# 31_Power2.net
KiCad netlist of a schematic drawn in Altium Designer
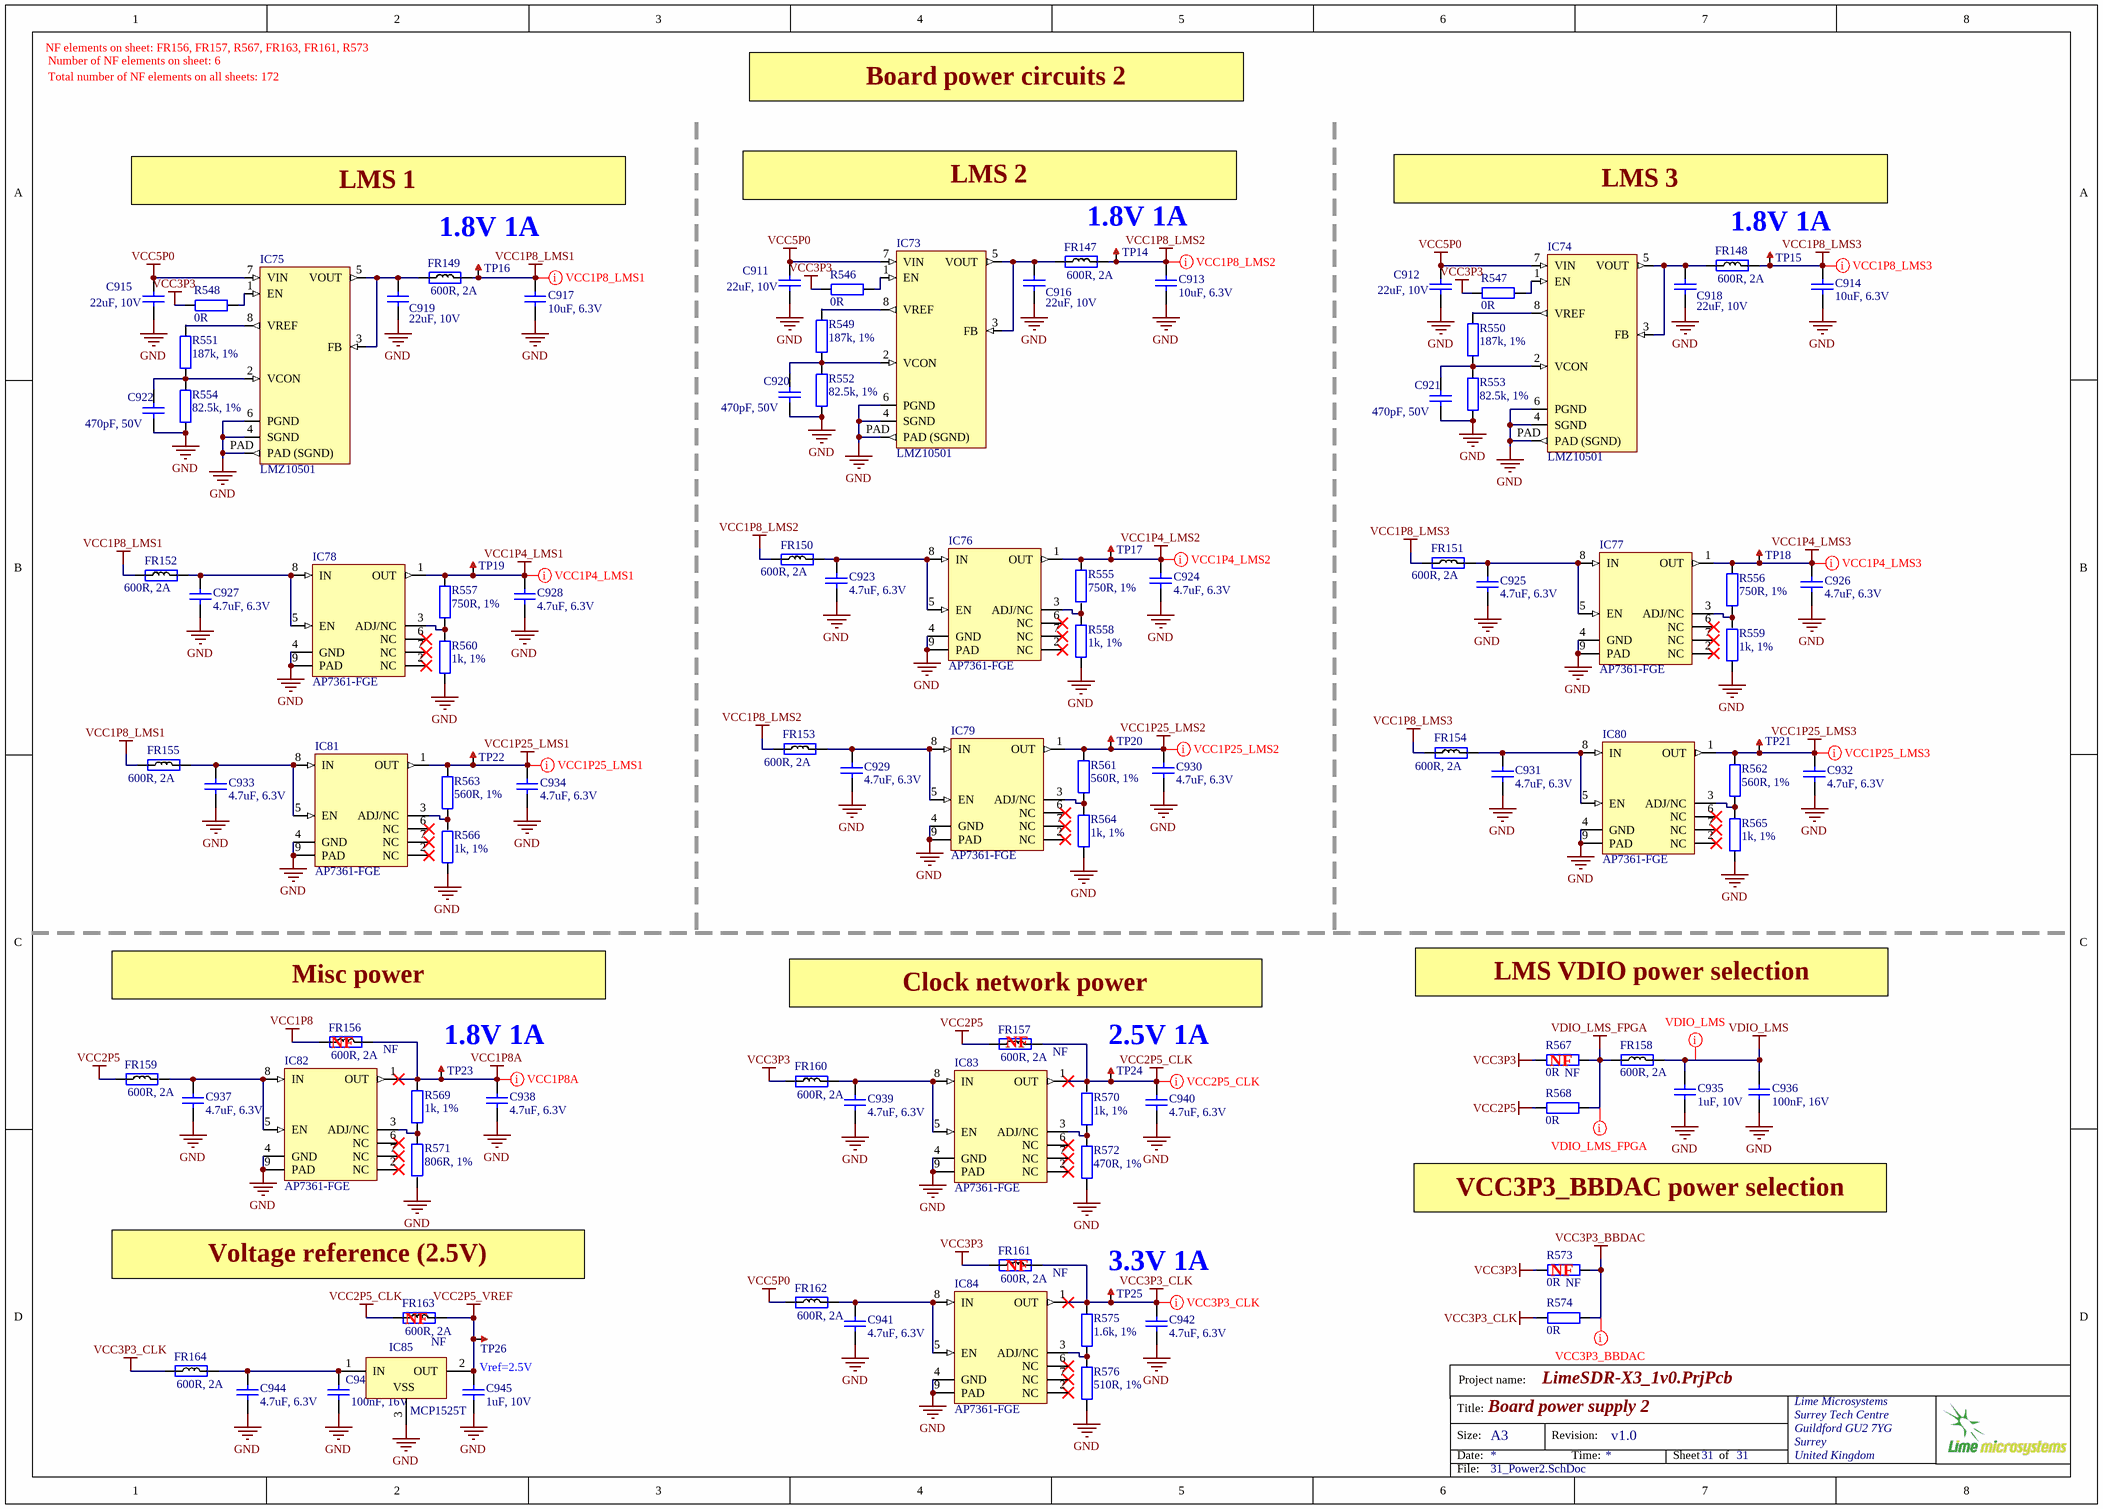
[diagram p0: 31_Power2.SchDoc]

(export (version "E")
  (design (tool "Eeschema 10.0.6"))
  (components
    (comp (ref "C911")
      (value "22uF, 10V")
      (footprint "CAP0603")
      (fields (field (name "TOLERANCE") "20 %") (field (name "MANUFACTURER") "TDK Corporation"))
      (libsource (lib "LimeFPGAboard_schLib") (part "Cap_0603"))
    )
    (comp (ref "C912")
      (value "22uF, 10V")
      (footprint "CAP0603")
      (fields (field (name "TOLERANCE") "20 %") (field (name "MANUFACTURER") "TDK Corporation"))
      (libsource (lib "LimeFPGAboard_schLib") (part "Cap_0603"))
    )
    (comp (ref "C913")
      (value "10uF, 6.3V")
      (footprint "CAP0603")
      (fields (field (name "TOLERANCE") "±20%") (field (name "MANUFACTURER") "Yageo"))
      (libsource (lib "LimeFPGAboard_schLib") (part "Cap_0603"))
    )
    (comp (ref "C914")
      (value "10uF, 6.3V")
      (footprint "CAP0603")
      (fields (field (name "TOLERANCE") "±20%") (field (name "MANUFACTURER") "Yageo"))
      (libsource (lib "LimeFPGAboard_schLib") (part "Cap_0603"))
    )
    (comp (ref "C915")
      (value "22uF, 10V")
      (footprint "CAP0603")
      (fields (field (name "TOLERANCE") "20 %") (field (name "MANUFACTURER") "TDK Corporation"))
      (libsource (lib "LimeFPGAboard_schLib") (part "Cap_0603"))
    )
    (comp (ref "C916")
      (value "22uF, 10V")
      (footprint "CAP0603")
      (fields (field (name "TOLERANCE") "20 %") (field (name "MANUFACTURER") "TDK Corporation"))
      (libsource (lib "LimeFPGAboard_schLib") (part "Cap_0603"))
    )
    (comp (ref "C917")
      (value "10uF, 6.3V")
      (footprint "CAP0603")
      (fields (field (name "TOLERANCE") "±20%") (field (name "MANUFACTURER") "Yageo"))
      (libsource (lib "") (part "Cap_0603_1"))
    )
    (comp (ref "C918")
      (value "22uF, 10V")
      (footprint "CAP0603")
      (fields (field (name "TOLERANCE") "20 %") (field (name "MANUFACTURER") "TDK Corporation"))
      (libsource (lib "LimeFPGAboard_schLib") (part "Cap_0603"))
    )
    (comp (ref "C919")
      (value "22uF, 10V")
      (footprint "CAP0603")
      (fields (field (name "TOLERANCE") "20 %") (field (name "MANUFACTURER") "TDK Corporation"))
      (libsource (lib "LimeFPGAboard_schLib") (part "Cap_0603"))
    )
    (comp (ref "C920")
      (value "470pF, 50V")
      (footprint "CAP0402")
      (fields
        (field (name "TOLERANCE") "±5%")
        (field (name "MANUFACTURER") "TDK Corporation")
        (field (name "MANUFACTURER PART NUMBER") "C1005C0G1H471J050BA")
      )
      (libsource (lib "") (part "Cap_0402_5"))
    )
    (comp (ref "C921")
      (value "470pF, 50V")
      (footprint "CAP0402")
      (fields
        (field (name "TOLERANCE") "±5%")
        (field (name "MANUFACTURER") "TDK Corporation")
        (field (name "MANUFACTURER PART NUMBER") "C1005C0G1H471J050BA")
      )
      (libsource (lib "") (part "Cap_0402_5"))
    )
    (comp (ref "C922")
      (value "470pF, 50V")
      (footprint "CAP0402")
      (fields
        (field (name "TOLERANCE") "±5%")
        (field (name "MANUFACTURER") "TDK Corporation")
        (field (name "MANUFACTURER PART NUMBER") "C1005C0G1H471J050BA")
      )
      (libsource (lib "") (part "Cap_0402_5"))
    )
    (comp (ref "C923")
      (value "4.7uF, 6.3V")
      (footprint "CAP0402")
      (fields
        (field (name "MANUFACTURER") "Murata Electronics North America")
        (field (name "TOLERANCE") "±20%")
      )
      (libsource (lib "") (part "Cap_0402_1"))
    )
    (comp (ref "C924")
      (value "4.7uF, 6.3V")
      (footprint "CAP0402")
      (fields
        (field (name "MANUFACTURER") "Murata Electronics North America")
        (field (name "TOLERANCE") "±20%")
      )
      (libsource (lib "") (part "Cap_0402_1"))
    )
    (comp (ref "C925")
      (value "4.7uF, 6.3V")
      (footprint "CAP0402")
      (fields
        (field (name "MANUFACTURER") "Murata Electronics North America")
        (field (name "TOLERANCE") "±20%")
      )
      (libsource (lib "") (part "Cap_0402_1"))
    )
    (comp (ref "C926")
      (value "4.7uF, 6.3V")
      (footprint "CAP0402")
      (fields
        (field (name "MANUFACTURER") "Murata Electronics North America")
        (field (name "TOLERANCE") "±20%")
      )
      (libsource (lib "") (part "Cap_0402_1"))
    )
    (comp (ref "C927")
      (value "4.7uF, 6.3V")
      (footprint "CAP0402")
      (fields
        (field (name "MANUFACTURER") "Murata Electronics North America")
        (field (name "TOLERANCE") "±20%")
      )
      (libsource (lib "") (part "Cap_0402_2"))
    )
    (comp (ref "C928")
      (value "4.7uF, 6.3V")
      (footprint "CAP0402")
      (fields
        (field (name "MANUFACTURER") "Murata Electronics North America")
        (field (name "TOLERANCE") "±20%")
      )
      (libsource (lib "") (part "Cap_0402_2"))
    )
    (comp (ref "C929")
      (value "4.7uF, 6.3V")
      (footprint "CAP0402")
      (fields
        (field (name "MANUFACTURER") "Murata Electronics North America")
        (field (name "TOLERANCE") "±20%")
      )
      (libsource (lib "") (part "Cap_0402_1"))
    )
    (comp (ref "C930")
      (value "4.7uF, 6.3V")
      (footprint "CAP0402")
      (fields
        (field (name "MANUFACTURER") "Murata Electronics North America")
        (field (name "TOLERANCE") "±20%")
      )
      (libsource (lib "") (part "Cap_0402_1"))
    )
    (comp (ref "C931")
      (value "4.7uF, 6.3V")
      (footprint "CAP0402")
      (fields
        (field (name "MANUFACTURER") "Murata Electronics North America")
        (field (name "TOLERANCE") "±20%")
      )
      (libsource (lib "") (part "Cap_0402_5"))
    )
    (comp (ref "C932")
      (value "4.7uF, 6.3V")
      (footprint "CAP0402")
      (fields
        (field (name "MANUFACTURER") "Murata Electronics North America")
        (field (name "TOLERANCE") "±20%")
      )
      (libsource (lib "") (part "Cap_0402_1"))
    )
    (comp (ref "C933")
      (value "4.7uF, 6.3V")
      (footprint "CAP0402")
      (fields
        (field (name "MANUFACTURER") "Murata Electronics North America")
        (field (name "TOLERANCE") "±20%")
      )
      (libsource (lib "") (part "Cap_0402_1"))
    )
    (comp (ref "C934")
      (value "4.7uF, 6.3V")
      (footprint "CAP0402")
      (fields
        (field (name "MANUFACTURER") "Murata Electronics North America")
        (field (name "TOLERANCE") "±20%")
      )
      (libsource (lib "") (part "Cap_0402_2"))
    )
    (comp (ref "C935")
      (value "1uF, 10V")
      (footprint "CAP0402")
      (fields (field (name "MANUFACTURER") "TDK"))
      (libsource (lib "") (part "Cap_0402_2"))
    )
    (comp (ref "C936")
      (value "100nF, 16V")
      (footprint "CAP0402")
      (fields (field (name "MANUFACTURER") "Murata Electronics") (field (name "TOLERANCE") "10 %"))
      (libsource (lib "") (part "Cap_0402_2"))
    )
    (comp (ref "C937")
      (value "4.7uF, 6.3V")
      (footprint "CAP0402")
      (fields
        (field (name "MANUFACTURER") "Murata Electronics North America")
        (field (name "TOLERANCE") "±20%")
      )
      (libsource (lib "") (part "Cap_0402_3"))
    )
    (comp (ref "C938")
      (value "4.7uF, 6.3V")
      (footprint "CAP0402")
      (fields
        (field (name "MANUFACTURER") "Murata Electronics North America")
        (field (name "TOLERANCE") "±20%")
      )
      (libsource (lib "") (part "Cap_0402_3"))
    )
    (comp (ref "C939")
      (value "4.7uF, 6.3V")
      (footprint "CAP0402")
      (fields
        (field (name "MANUFACTURER") "Murata Electronics North America")
        (field (name "TOLERANCE") "±20%")
      )
      (libsource (lib "") (part "Cap_0402_1"))
    )
    (comp (ref "C940")
      (value "4.7uF, 6.3V")
      (footprint "CAP0402")
      (fields
        (field (name "MANUFACTURER") "Murata Electronics North America")
        (field (name "TOLERANCE") "±20%")
      )
      (libsource (lib "") (part "Cap_0402_2"))
    )
    (comp (ref "C941")
      (value "4.7uF, 6.3V")
      (footprint "CAP0402")
      (fields
        (field (name "MANUFACTURER") "Murata Electronics North America")
        (field (name "TOLERANCE") "±20%")
      )
      (libsource (lib "") (part "Cap_0402_4"))
    )
    (comp (ref "C942")
      (value "4.7uF, 6.3V")
      (footprint "CAP0402")
      (fields
        (field (name "MANUFACTURER") "Murata Electronics North America")
        (field (name "TOLERANCE") "±20%")
      )
      (libsource (lib "") (part "Cap_0402_3"))
    )
    (comp (ref "C943")
      (value "100nF, 16V")
      (footprint "CAP0402")
      (fields (field (name "MANUFACTURER") "Murata Electronics") (field (name "TOLERANCE") "10 %"))
      (libsource (lib "LimeMicroAltiumLib_schLib") (part "Cap_0402"))
    )
    (comp (ref "C944")
      (value "4.7uF, 6.3V")
      (footprint "CAP0402")
      (fields
        (field (name "MANUFACTURER") "Murata Electronics North America")
        (field (name "TOLERANCE") "±20%")
      )
      (libsource (lib "LimeMicroAltiumLib_schLib") (part "Cap_0402"))
    )
    (comp (ref "C945")
      (value "1uF, 10V")
      (footprint "CAP0402")
      (fields (field (name "MANUFACTURER") "TDK"))
      (libsource (lib "LimeMicroAltiumLib_schLib") (part "Cap_0402"))
    )
    (comp (ref "FR147")
      (value "600R, 2A")
      (footprint "RES0805")
      (fields (field (name "MANUFACTURER") "TDK Corporation"))
      (libsource (lib "LimeMicroAltiumLib_schLib") (part "Ferrite"))
    )
    (comp (ref "FR148")
      (value "600R, 2A")
      (footprint "RES0805")
      (fields (field (name "MANUFACTURER") "TDK Corporation"))
      (libsource (lib "LimeMicroAltiumLib_schLib") (part "Ferrite"))
    )
    (comp (ref "FR149")
      (value "600R, 2A")
      (footprint "RES0805")
      (fields (field (name "MANUFACTURER") "TDK Corporation"))
      (libsource (lib "LimeMicroAltiumLib_schLib") (part "Ferrite"))
    )
    (comp (ref "FR150")
      (value "600R, 2A")
      (footprint "RES0805")
      (fields (field (name "MANUFACTURER") "TDK Corporation"))
      (libsource (lib "LimeMicroAltiumLib_schLib") (part "Ferrite"))
    )
    (comp (ref "FR151")
      (value "600R, 2A")
      (footprint "RES0805")
      (fields (field (name "MANUFACTURER") "TDK Corporation"))
      (libsource (lib "LimeMicroAltiumLib_schLib") (part "Ferrite"))
    )
    (comp (ref "FR152")
      (value "600R, 2A")
      (footprint "RES0805")
      (fields (field (name "MANUFACTURER") "TDK Corporation"))
      (libsource (lib "LimeMicroAltiumLib_schLib") (part "Ferrite"))
    )
    (comp (ref "FR153")
      (value "600R, 2A")
      (footprint "RES0805")
      (fields (field (name "MANUFACTURER") "TDK Corporation"))
      (libsource (lib "LimeMicroAltiumLib_schLib") (part "Ferrite"))
    )
    (comp (ref "FR154")
      (value "600R, 2A")
      (footprint "RES0805")
      (fields (field (name "MANUFACTURER") "TDK Corporation"))
      (libsource (lib "LimeMicroAltiumLib_schLib") (part "Ferrite"))
    )
    (comp (ref "FR155")
      (value "600R, 2A")
      (footprint "RES0805")
      (fields (field (name "MANUFACTURER") "TDK Corporation"))
      (libsource (lib "LimeMicroAltiumLib_schLib") (part "Ferrite"))
    )
    (comp (ref "FR156")
      (value "600R, 2A")
      (footprint "RES0805")
      (fields (field (name "MANUFACTURER") "TDK Corporation") (field (name "ASSEMBLY INFO") "NF"))
      (libsource (lib "LimeMicroAltiumLib_schLib") (part "Ferrite"))
    )
    (comp (ref "FR157")
      (value "600R, 2A")
      (footprint "RES0805")
      (fields (field (name "MANUFACTURER") "TDK Corporation") (field (name "ASSEMBLY INFO") "NF"))
      (libsource (lib "LimeMicroAltiumLib_schLib") (part "Ferrite"))
    )
    (comp (ref "FR158")
      (value "600R, 2A")
      (footprint "RES0805")
      (fields (field (name "MANUFACTURER") "TDK Corporation"))
      (libsource (lib "LimeMicroAltiumLib_schLib") (part "Ferrite"))
    )
    (comp (ref "FR159")
      (value "600R, 2A")
      (footprint "RES0805")
      (fields (field (name "MANUFACTURER") "TDK Corporation"))
      (libsource (lib "LimeMicroAltiumLib_schLib") (part "Ferrite"))
    )
    (comp (ref "FR160")
      (value "600R, 2A")
      (footprint "RES0805")
      (fields (field (name "MANUFACTURER") "TDK Corporation"))
      (libsource (lib "LimeMicroAltiumLib_schLib") (part "Ferrite"))
    )
    (comp (ref "FR161")
      (value "600R, 2A")
      (footprint "RES0805")
      (fields (field (name "MANUFACTURER") "TDK Corporation") (field (name "ASSEMBLY INFO") "NF"))
      (libsource (lib "LimeMicroAltiumLib_schLib") (part "Ferrite"))
    )
    (comp (ref "FR162")
      (value "600R, 2A")
      (footprint "RES0805")
      (fields (field (name "MANUFACTURER") "TDK Corporation"))
      (libsource (lib "LimeMicroAltiumLib_schLib") (part "Ferrite"))
    )
    (comp (ref "FR163")
      (value "600R, 2A")
      (footprint "RES0805")
      (fields (field (name "MANUFACTURER") "TDK Corporation") (field (name "ASSEMBLY INFO") "NF"))
      (libsource (lib "LimeMicroAltiumLib_schLib") (part "Ferrite"))
    )
    (comp (ref "FR164")
      (value "600R, 2A")
      (footprint "RES0805")
      (fields (field (name "MANUFACTURER") "TDK Corporation"))
      (libsource (lib "LimeMicroAltiumLib_schLib") (part "Ferrite"))
    )
    (comp (ref "IC73")
      (value "LMZ10501")
      (footprint "LMZ10501")
      (fields (field (name "MANUFACTURER") "Texas Instruments"))
      (libsource (lib "LimeMicroAltiumLib_schLib") (part "LMZ10501"))
    )
    (comp (ref "IC74")
      (value "LMZ10501")
      (footprint "LMZ10501")
      (fields (field (name "MANUFACTURER") "Texas Instruments"))
      (libsource (lib "") (part "LMZ10501_2"))
    )
    (comp (ref "IC75")
      (value "LMZ10501")
      (footprint "LMZ10501")
      (fields (field (name "MANUFACTURER") "Texas Instruments"))
      (libsource (lib "") (part "LMZ10501_1"))
    )
    (comp (ref "IC76")
      (value "AP7361-FGE")
      (footprint "AP7361")
      (fields (field (name "MANUFACTURER") "Diodes Incorporated"))
      (libsource (lib "") (part "AP7361_2"))
    )
    (comp (ref "IC77")
      (value "AP7361-FGE")
      (footprint "AP7361")
      (fields (field (name "MANUFACTURER") "Diodes Incorporated"))
      (libsource (lib "LimeMicroAltiumLib_schLib") (part "AP7361"))
    )
    (comp (ref "IC78")
      (value "AP7361-FGE")
      (footprint "AP7361")
      (fields (field (name "MANUFACTURER") "Diodes Incorporated"))
      (libsource (lib "") (part "AP7361_6"))
    )
    (comp (ref "IC79")
      (value "AP7361-FGE")
      (footprint "AP7361")
      (fields (field (name "MANUFACTURER") "Diodes Incorporated"))
      (libsource (lib "") (part "AP7361_4"))
    )
    (comp (ref "IC80")
      (value "AP7361-FGE")
      (footprint "AP7361")
      (fields (field (name "MANUFACTURER") "Diodes Incorporated"))
      (libsource (lib "") (part "AP7361_5"))
    )
    (comp (ref "IC81")
      (value "AP7361-FGE")
      (footprint "AP7361")
      (fields (field (name "MANUFACTURER") "Diodes Incorporated"))
      (libsource (lib "") (part "AP7361_7"))
    )
    (comp (ref "IC82")
      (value "AP7361-FGE")
      (footprint "AP7361")
      (fields (field (name "MANUFACTURER") "Diodes Incorporated"))
      (libsource (lib "") (part "AP7361_1"))
    )
    (comp (ref "IC83")
      (value "AP7361-FGE")
      (footprint "AP7361")
      (fields (field (name "MANUFACTURER") "Diodes Incorporated"))
      (libsource (lib "") (part "AP7361_8"))
    )
    (comp (ref "IC84")
      (value "AP7361-FGE")
      (footprint "AP7361")
      (fields (field (name "MANUFACTURER") "Diodes Incorporated"))
      (libsource (lib "") (part "AP7361_3"))
    )
    (comp (ref "IC85")
      (value "MCP1525T")
      (footprint "SOT23-3_v2")
      (description "2.5V Voltage Reference, 3-Pin SOT-23, Industrial Temperature, Tape and Reel")
      (fields (field (name "MANUFACTURER") "Microchip Technology") (field (name "TOLERANCE") "±1%"))
      (libsource (lib "LimeMicroAltiumLib_schLib") (part "MCP1525T-I/TT"))
    )
    (comp (ref "R546")
      (value "0R")
      (footprint "RES0402")
      (fields (field (name "MANUFACTURER") "Yageo") (field (name "TOLERANCE") "Jumper"))
      (libsource (lib "LimeMicroAltiumLib_schLib") (part "Res_0402"))
    )
    (comp (ref "R547")
      (value "0R")
      (footprint "RES0402")
      (fields (field (name "MANUFACTURER") "Yageo") (field (name "TOLERANCE") "Jumper"))
      (libsource (lib "LimeMicroAltiumLib_schLib") (part "Res_0402"))
    )
    (comp (ref "R548")
      (value "0R")
      (footprint "RES0402")
      (fields (field (name "MANUFACTURER") "Yageo") (field (name "TOLERANCE") "Jumper"))
      (libsource (lib "LimeMicroAltiumLib_schLib") (part "Res_0402"))
    )
    (comp (ref "R549")
      (value "187k, 1%")
      (footprint "RES0402")
      (fields (field (name "TOLERANCE") "±1%") (field (name "MANUFACTURER") "Yageo"))
      (libsource (lib "LimeMicroAltiumLib_schLib") (part "Res_0402"))
    )
    (comp (ref "R550")
      (value "187k, 1%")
      (footprint "RES0402")
      (fields (field (name "TOLERANCE") "±1%") (field (name "MANUFACTURER") "Yageo"))
      (libsource (lib "LimeMicroAltiumLib_schLib") (part "Res_0402"))
    )
    (comp (ref "R551")
      (value "187k, 1%")
      (footprint "RES0402")
      (fields (field (name "TOLERANCE") "±1%") (field (name "MANUFACTURER") "Yageo"))
      (libsource (lib "LimeMicroAltiumLib_schLib") (part "Res_0402"))
    )
    (comp (ref "R552")
      (value "82.5k, 1%")
      (footprint "RES0402")
      (fields (field (name "TOLERANCE") "±1%") (field (name "MANUFACTURER") "Yageo"))
      (libsource (lib "LimeMicroAltiumLib_schLib") (part "Res_0402"))
    )
    (comp (ref "R553")
      (value "82.5k, 1%")
      (footprint "RES0402")
      (fields (field (name "TOLERANCE") "±1%") (field (name "MANUFACTURER") "Yageo"))
      (libsource (lib "LimeMicroAltiumLib_schLib") (part "Res_0402"))
    )
    (comp (ref "R554")
      (value "82.5k, 1%")
      (footprint "RES0402")
      (fields (field (name "TOLERANCE") "±1%") (field (name "MANUFACTURER") "Yageo"))
      (libsource (lib "LimeMicroAltiumLib_schLib") (part "Res_0402"))
    )
    (comp (ref "R555")
      (value "750R, 1%")
      (footprint "RES0402")
      (fields (field (name "TOLERANCE") "±1%") (field (name "MANUFACTURER") "Yageo"))
      (libsource (lib "LimeMicroAltiumLib_schLib") (part "Res_0402"))
    )
    (comp (ref "R556")
      (value "750R, 1%")
      (footprint "RES0402")
      (fields (field (name "TOLERANCE") "±1%") (field (name "MANUFACTURER") "Yageo"))
      (libsource (lib "LimeMicroAltiumLib_schLib") (part "Res_0402"))
    )
    (comp (ref "R557")
      (value "750R, 1%")
      (footprint "RES0402")
      (fields (field (name "TOLERANCE") "±1%") (field (name "MANUFACTURER") "Yageo"))
      (libsource (lib "LimeMicroAltiumLib_schLib") (part "Res_0402"))
    )
    (comp (ref "R558")
      (value "1k, 1%")
      (footprint "RES0402")
      (fields (field (name "MANUFACTURER") "Stackpole Electronics Inc") (field (name "TOLERANCE") "±1%"))
      (libsource (lib "LimeMicroAltiumLib_schLib") (part "Res_0402"))
    )
    (comp (ref "R559")
      (value "1k, 1%")
      (footprint "RES0402")
      (fields (field (name "MANUFACTURER") "Stackpole Electronics Inc") (field (name "TOLERANCE") "±1%"))
      (libsource (lib "LimeMicroAltiumLib_schLib") (part "Res_0402"))
    )
    (comp (ref "R560")
      (value "1k, 1%")
      (footprint "RES0402")
      (fields (field (name "MANUFACTURER") "Stackpole Electronics Inc") (field (name "TOLERANCE") "±1%"))
      (libsource (lib "LimeMicroAltiumLib_schLib") (part "Res_0402"))
    )
    (comp (ref "R561")
      (value "560R, 1%")
      (footprint "RES0402")
      (fields (field (name "TOLERANCE") "±1%") (field (name "MANUFACTURER") "Vishay Dale"))
      (libsource (lib "LimeMicroAltiumLib_schLib") (part "Res_0402"))
    )
    (comp (ref "R562")
      (value "560R, 1%")
      (footprint "RES0402")
      (fields (field (name "TOLERANCE") "±1%") (field (name "MANUFACTURER") "Vishay Dale"))
      (libsource (lib "LimeMicroAltiumLib_schLib") (part "Res_0402"))
    )
    (comp (ref "R563")
      (value "560R, 1%")
      (footprint "RES0402")
      (fields (field (name "TOLERANCE") "±1%") (field (name "MANUFACTURER") "Vishay Dale"))
      (libsource (lib "LimeMicroAltiumLib_schLib") (part "Res_0402"))
    )
    (comp (ref "R564")
      (value "1k, 1%")
      (footprint "RES0402")
      (fields (field (name "MANUFACTURER") "Stackpole Electronics Inc") (field (name "TOLERANCE") "±1%"))
      (libsource (lib "LimeMicroAltiumLib_schLib") (part "Res_0402"))
    )
    (comp (ref "R565")
      (value "1k, 1%")
      (footprint "RES0402")
      (fields (field (name "MANUFACTURER") "Stackpole Electronics Inc") (field (name "TOLERANCE") "±1%"))
      (libsource (lib "LimeMicroAltiumLib_schLib") (part "Res_0402"))
    )
    (comp (ref "R566")
      (value "1k, 1%")
      (footprint "RES0402")
      (fields (field (name "MANUFACTURER") "Stackpole Electronics Inc") (field (name "TOLERANCE") "±1%"))
      (libsource (lib "LimeMicroAltiumLib_schLib") (part "Res_0402"))
    )
    (comp (ref "R567")
      (value "0R")
      (footprint "RES0402")
      (fields
        (field (name "ASSEMBLY INFO") "NF")
        (field (name "MANUFACTURER") "Yageo")
        (field (name "TOLERANCE") "Jumper")
      )
      (libsource (lib "LimeMicroAltiumLib_schLib") (part "Res_0402"))
    )
    (comp (ref "R568")
      (value "0R")
      (footprint "RES0402")
      (fields (field (name "MANUFACTURER") "Yageo") (field (name "TOLERANCE") "Jumper"))
      (libsource (lib "LimeMicroAltiumLib_schLib") (part "Res_0402"))
    )
    (comp (ref "R569")
      (value "1k, 1%")
      (footprint "RES0402")
      (fields (field (name "MANUFACTURER") "Stackpole Electronics Inc") (field (name "TOLERANCE") "±1%"))
      (libsource (lib "LimeMicroAltiumLib_schLib") (part "Res_0402"))
    )
    (comp (ref "R570")
      (value "1k, 1%")
      (footprint "RES0402")
      (fields (field (name "MANUFACTURER") "Stackpole Electronics Inc") (field (name "TOLERANCE") "±1%"))
      (libsource (lib "LimeMicroAltiumLib_schLib") (part "Res_0402"))
    )
    (comp (ref "R571")
      (value "806R, 1%")
      (footprint "RES0402")
      (fields (field (name "TOLERANCE") "±1%") (field (name "MANUFACTURER") "Stackpole Electronics Inc"))
      (libsource (lib "LimeMicroAltiumLib_schLib") (part "Res_0402"))
    )
    (comp (ref "R572")
      (value "470R, 1%")
      (footprint "RES0402")
      (fields (field (name "MANUFACTURER") "Yageo") (field (name "TOLERANCE") "1%"))
      (libsource (lib "LimeMicroAltiumLib_schLib") (part "Res_0402"))
    )
    (comp (ref "R573")
      (value "0R")
      (footprint "RES0402")
      (fields
        (field (name "ASSEMBLY INFO") "NF")
        (field (name "MANUFACTURER") "Yageo")
        (field (name "TOLERANCE") "Jumper")
      )
      (libsource (lib "LimeMicroAltiumLib_schLib") (part "Res_0402"))
    )
    (comp (ref "R574")
      (value "0R")
      (footprint "RES0402")
      (fields (field (name "MANUFACTURER") "Yageo") (field (name "TOLERANCE") "Jumper"))
      (libsource (lib "LimeMicroAltiumLib_schLib") (part "Res_0402"))
    )
    (comp (ref "R575")
      (value "1.6k, 1%")
      (footprint "RES0402")
      (fields (field (name "TOLERANCE") "±1%") (field (name "MANUFACTURER") "Yageo"))
      (libsource (lib "LimeMicroAltiumLib_schLib") (part "Res_0402"))
    )
    (comp (ref "R576")
      (value "510R, 1%")
      (footprint "RES0402")
      (fields (field (name "TOLERANCE") "±1%") (field (name "MANUFACTURER") "Yageo"))
      (libsource (lib "LimeMicroAltiumLib_schLib") (part "Res_0402"))
    )
    (comp (ref "TP14")
      (value "TESTPOINT_PAD")
      (footprint "TP_PAD_1p5MM")
      (description "Test Point PCB mount Miniature White")
      (libsource (lib "LimeMicroAltiumLib_schLib_r04") (part "TESTPOINT_PAD"))
    )
    (comp (ref "TP15")
      (value "TESTPOINT_PAD")
      (footprint "TP_PAD_1p5MM")
      (description "Test Point PCB mount Miniature White")
      (libsource (lib "LimeMicroAltiumLib_schLib_r04") (part "TESTPOINT_PAD"))
    )
    (comp (ref "TP16")
      (value "TESTPOINT_PAD")
      (footprint "TP_PAD_1p5MM")
      (description "Test Point PCB mount Miniature White")
      (libsource (lib "LimeMicroAltiumLib_schLib_r04") (part "TESTPOINT_PAD"))
    )
    (comp (ref "TP17")
      (value "TESTPOINT_PAD")
      (footprint "TP_PAD_1p5MM")
      (description "Test Point PCB mount Miniature White")
      (libsource (lib "LimeMicroAltiumLib_schLib_r04") (part "TESTPOINT_PAD"))
    )
    (comp (ref "TP18")
      (value "TESTPOINT_PAD")
      (footprint "TP_PAD_1p5MM")
      (description "Test Point PCB mount Miniature White")
      (libsource (lib "LimeMicroAltiumLib_schLib_r04") (part "TESTPOINT_PAD"))
    )
    (comp (ref "TP19")
      (value "TESTPOINT_PAD")
      (footprint "TP_PAD_1p5MM")
      (description "Test Point PCB mount Miniature White")
      (libsource (lib "LimeMicroAltiumLib_schLib_r04") (part "TESTPOINT_PAD"))
    )
    (comp (ref "TP20")
      (value "TESTPOINT_PAD")
      (footprint "TP_PAD_1p5MM")
      (description "Test Point PCB mount Miniature White")
      (libsource (lib "LimeMicroAltiumLib_schLib_r04") (part "TESTPOINT_PAD"))
    )
    (comp (ref "TP21")
      (value "TESTPOINT_PAD")
      (footprint "TP_PAD_1p5MM")
      (description "Test Point PCB mount Miniature White")
      (libsource (lib "LimeMicroAltiumLib_schLib_r04") (part "TESTPOINT_PAD"))
    )
    (comp (ref "TP22")
      (value "TESTPOINT_PAD")
      (footprint "TP_PAD_1p5MM")
      (description "Test Point PCB mount Miniature White")
      (libsource (lib "LimeMicroAltiumLib_schLib_r04") (part "TESTPOINT_PAD"))
    )
    (comp (ref "TP23")
      (value "TESTPOINT_PAD")
      (footprint "TP_PAD_1p5MM")
      (description "Test Point PCB mount Miniature White")
      (libsource (lib "LimeMicroAltiumLib_schLib_r04") (part "TESTPOINT_PAD"))
    )
    (comp (ref "TP24")
      (value "TESTPOINT_PAD")
      (footprint "TP_PAD_1p5MM")
      (description "Test Point PCB mount Miniature White")
      (libsource (lib "LimeMicroAltiumLib_schLib_r04") (part "TESTPOINT_PAD"))
    )
    (comp (ref "TP25")
      (value "TESTPOINT_PAD")
      (footprint "TP_PAD_1p5MM")
      (description "Test Point PCB mount Miniature White")
      (libsource (lib "LimeMicroAltiumLib_schLib_r04") (part "TESTPOINT_PAD"))
    )
    (comp (ref "TP26")
      (value "TESTPOINT_PAD")
      (footprint "TP_PAD_1p5MM")
      (description "Test Point PCB mount Miniature White")
      (libsource (lib "LimeMicroAltiumLib_schLib_r04") (part "TESTPOINT_PAD"))
    )
  )
  (nets
    (net (code "1") (name "GND") (class "Default")
      (node (ref "C911") (pin "1") (pinfunction "1_1") (pintype "passive"))
      (node (ref "C912") (pin "1") (pinfunction "1_1") (pintype "passive"))
      (node (ref "C913") (pin "1") (pinfunction "1_1") (pintype "passive"))
      (node (ref "C914") (pin "1") (pinfunction "1_1") (pintype "passive"))
      (node (ref "C915") (pin "1") (pinfunction "1_1") (pintype "passive"))
      (node (ref "C916") (pin "1") (pinfunction "1_1") (pintype "passive"))
      (node (ref "C917") (pin "1") (pinfunction "1_1") (pintype "passive"))
      (node (ref "C918") (pin "1") (pinfunction "1_1") (pintype "passive"))
      (node (ref "C919") (pin "1") (pinfunction "1_1") (pintype "passive"))
      (node (ref "C920") (pin "2") (pinfunction "2_2") (pintype "passive"))
      (node (ref "C921") (pin "2") (pinfunction "2_2") (pintype "passive"))
      (node (ref "C922") (pin "2") (pinfunction "2_2") (pintype "passive"))
      (node (ref "C923") (pin "1") (pinfunction "1_1") (pintype "passive"))
      (node (ref "C924") (pin "1") (pinfunction "1_1") (pintype "passive"))
      (node (ref "C925") (pin "1") (pinfunction "1_1") (pintype "passive"))
      (node (ref "C926") (pin "1") (pinfunction "1_1") (pintype "passive"))
      (node (ref "C927") (pin "1") (pinfunction "1_1") (pintype "passive"))
      (node (ref "C928") (pin "1") (pinfunction "1_1") (pintype "passive"))
      (node (ref "C929") (pin "1") (pinfunction "1_1") (pintype "passive"))
      (node (ref "C930") (pin "1") (pinfunction "1_1") (pintype "passive"))
      (node (ref "C931") (pin "1") (pinfunction "1_1") (pintype "passive"))
      (node (ref "C932") (pin "1") (pinfunction "1_1") (pintype "passive"))
      (node (ref "C933") (pin "1") (pinfunction "1_1") (pintype "passive"))
      (node (ref "C934") (pin "1") (pinfunction "1_1") (pintype "passive"))
      (node (ref "C935") (pin "1") (pinfunction "1_1") (pintype "passive"))
      (node (ref "C936") (pin "2") (pinfunction "2_2") (pintype "passive"))
      (node (ref "C937") (pin "1") (pinfunction "1_1") (pintype "passive"))
      (node (ref "C938") (pin "1") (pinfunction "1_1") (pintype "passive"))
      (node (ref "C939") (pin "1") (pinfunction "1_1") (pintype "passive"))
      (node (ref "C940") (pin "1") (pinfunction "1_1") (pintype "passive"))
      (node (ref "C941") (pin "1") (pinfunction "1_1") (pintype "passive"))
      (node (ref "C942") (pin "1") (pinfunction "1_1") (pintype "passive"))
      (node (ref "C943") (pin "1") (pinfunction "1_1") (pintype "passive"))
      (node (ref "C944") (pin "1") (pinfunction "1_1") (pintype "passive"))
      (node (ref "C945") (pin "1") (pinfunction "1_1") (pintype "passive"))
      (node (ref "IC73") (pin "4") (pinfunction "SGND_4") (pintype "passive"))
      (node (ref "IC73") (pin "6") (pinfunction "PGND_6") (pintype "passive"))
      (node (ref "IC73") (pin "PAD") (pinfunction "PAD_(SGND)_PAD") (pintype "output"))
      (node (ref "IC74") (pin "4") (pinfunction "SGND_4") (pintype "passive"))
      (node (ref "IC74") (pin "6") (pinfunction "PGND_6") (pintype "passive"))
      (node (ref "IC74") (pin "PAD") (pinfunction "PAD_(SGND)_PAD") (pintype "output"))
      (node (ref "IC75") (pin "4") (pinfunction "SGND_4") (pintype "passive"))
      (node (ref "IC75") (pin "6") (pinfunction "PGND_6") (pintype "passive"))
      (node (ref "IC75") (pin "PAD") (pinfunction "PAD_(SGND)_PAD") (pintype "output"))
      (node (ref "IC76") (pin "4") (pinfunction "GND_4") (pintype "passive"))
      (node (ref "IC76") (pin "9") (pinfunction "PAD_9") (pintype "passive"))
      (node (ref "IC77") (pin "4") (pinfunction "GND_4") (pintype "passive"))
      (node (ref "IC77") (pin "9") (pinfunction "PAD_9") (pintype "passive"))
      (node (ref "IC78") (pin "4") (pinfunction "GND_4") (pintype "passive"))
      (node (ref "IC78") (pin "9") (pinfunction "PAD_9") (pintype "passive"))
      (node (ref "IC79") (pin "4") (pinfunction "GND_4") (pintype "passive"))
      (node (ref "IC79") (pin "9") (pinfunction "PAD_9") (pintype "passive"))
      (node (ref "IC80") (pin "4") (pinfunction "GND_4") (pintype "passive"))
      (node (ref "IC80") (pin "9") (pinfunction "PAD_9") (pintype "passive"))
      (node (ref "IC81") (pin "4") (pinfunction "GND_4") (pintype "passive"))
      (node (ref "IC81") (pin "9") (pinfunction "PAD_9") (pintype "passive"))
      (node (ref "IC82") (pin "4") (pinfunction "GND_4") (pintype "passive"))
      (node (ref "IC82") (pin "9") (pinfunction "PAD_9") (pintype "passive"))
      (node (ref "IC83") (pin "4") (pinfunction "GND_4") (pintype "passive"))
      (node (ref "IC83") (pin "9") (pinfunction "PAD_9") (pintype "passive"))
      (node (ref "IC84") (pin "4") (pinfunction "GND_4") (pintype "passive"))
      (node (ref "IC84") (pin "9") (pinfunction "PAD_9") (pintype "passive"))
      (node (ref "IC85") (pin "3") (pinfunction "VSS_3") (pintype "power_in"))
      (node (ref "R552") (pin "1") (pinfunction "1_1") (pintype "passive"))
      (node (ref "R553") (pin "1") (pinfunction "1_1") (pintype "passive"))
      (node (ref "R554") (pin "1") (pinfunction "1_1") (pintype "passive"))
      (node (ref "R558") (pin "1") (pinfunction "1_1") (pintype "passive"))
      (node (ref "R559") (pin "1") (pinfunction "1_1") (pintype "passive"))
      (node (ref "R560") (pin "1") (pinfunction "1_1") (pintype "passive"))
      (node (ref "R564") (pin "1") (pinfunction "1_1") (pintype "passive"))
      (node (ref "R565") (pin "1") (pinfunction "1_1") (pintype "passive"))
      (node (ref "R566") (pin "1") (pinfunction "1_1") (pintype "passive"))
      (node (ref "R571") (pin "2") (pinfunction "2_2") (pintype "passive"))
      (node (ref "R572") (pin "2") (pinfunction "2_2") (pintype "passive"))
      (node (ref "R576") (pin "2") (pinfunction "2_2") (pintype "passive"))
    )
    (net (code "2") (name "Net-(IC73-EN)") (class "Default")
      (node (ref "IC73") (pin "1") (pinfunction "EN_1") (pintype "input"))
      (node (ref "R546") (pin "2") (pinfunction "2_2") (pintype "passive"))
    )
    (net (code "3") (name "Net-(IC73-FB)") (class "Default")
      (node (ref "C916") (pin "2") (pinfunction "2_2") (pintype "passive"))
      (node (ref "FR147") (pin "1") (pinfunction "1_1") (pintype "passive"))
      (node (ref "IC73") (pin "3") (pinfunction "FB_3") (pintype "input"))
      (node (ref "IC73") (pin "5") (pinfunction "VOUT_5") (pintype "output"))
    )
    (net (code "4") (name "Net-(IC73-VCON)") (class "Default")
      (node (ref "C920") (pin "1") (pinfunction "1_1") (pintype "passive"))
      (node (ref "IC73") (pin "2") (pinfunction "VCON_2") (pintype "input"))
      (node (ref "R549") (pin "1") (pinfunction "1_1") (pintype "passive"))
      (node (ref "R552") (pin "2") (pinfunction "2_2") (pintype "passive"))
    )
    (net (code "5") (name "Net-(IC73-VREF)") (class "Default")
      (node (ref "IC73") (pin "8") (pinfunction "VREF_8") (pintype "output"))
      (node (ref "R549") (pin "2") (pinfunction "2_2") (pintype "passive"))
    )
    (net (code "6") (name "Net-(IC74-EN)") (class "Default")
      (node (ref "IC74") (pin "1") (pinfunction "EN_1") (pintype "input"))
      (node (ref "R547") (pin "2") (pinfunction "2_2") (pintype "passive"))
    )
    (net (code "7") (name "Net-(IC74-FB)") (class "Default")
      (node (ref "C918") (pin "2") (pinfunction "2_2") (pintype "passive"))
      (node (ref "FR148") (pin "1") (pinfunction "1_1") (pintype "passive"))
      (node (ref "IC74") (pin "3") (pinfunction "FB_3") (pintype "input"))
      (node (ref "IC74") (pin "5") (pinfunction "VOUT_5") (pintype "output"))
    )
    (net (code "8") (name "Net-(IC74-VCON)") (class "Default")
      (node (ref "C921") (pin "1") (pinfunction "1_1") (pintype "passive"))
      (node (ref "IC74") (pin "2") (pinfunction "VCON_2") (pintype "input"))
      (node (ref "R550") (pin "1") (pinfunction "1_1") (pintype "passive"))
      (node (ref "R553") (pin "2") (pinfunction "2_2") (pintype "passive"))
    )
    (net (code "9") (name "Net-(IC74-VREF)") (class "Default")
      (node (ref "IC74") (pin "8") (pinfunction "VREF_8") (pintype "output"))
      (node (ref "R550") (pin "2") (pinfunction "2_2") (pintype "passive"))
    )
    (net (code "10") (name "Net-(IC75-EN)") (class "Default")
      (node (ref "IC75") (pin "1") (pinfunction "EN_1") (pintype "input"))
      (node (ref "R548") (pin "2") (pinfunction "2_2") (pintype "passive"))
    )
    (net (code "11") (name "Net-(IC75-FB)") (class "Default")
      (node (ref "C919") (pin "2") (pinfunction "2_2") (pintype "passive"))
      (node (ref "FR149") (pin "1") (pinfunction "1_1") (pintype "passive"))
      (node (ref "IC75") (pin "3") (pinfunction "FB_3") (pintype "input"))
      (node (ref "IC75") (pin "5") (pinfunction "VOUT_5") (pintype "output"))
    )
    (net (code "12") (name "Net-(IC75-VCON)") (class "Default")
      (node (ref "C922") (pin "1") (pinfunction "1_1") (pintype "passive"))
      (node (ref "IC75") (pin "2") (pinfunction "VCON_2") (pintype "input"))
      (node (ref "R551") (pin "1") (pinfunction "1_1") (pintype "passive"))
      (node (ref "R554") (pin "2") (pinfunction "2_2") (pintype "passive"))
    )
    (net (code "13") (name "Net-(IC75-VREF)") (class "Default")
      (node (ref "IC75") (pin "8") (pinfunction "VREF_8") (pintype "output"))
      (node (ref "R551") (pin "2") (pinfunction "2_2") (pintype "passive"))
    )
    (net (code "14") (name "Net-(IC76-ADJ{slash}NC)") (class "Default")
      (node (ref "IC76") (pin "3") (pinfunction "ADJ/NC_3") (pintype "passive"))
      (node (ref "R555") (pin "2") (pinfunction "2_2") (pintype "passive"))
      (node (ref "R558") (pin "2") (pinfunction "2_2") (pintype "passive"))
    )
    (net (code "15") (name "Net-(IC76-EN)") (class "Default")
      (node (ref "C923") (pin "2") (pinfunction "2_2") (pintype "passive"))
      (node (ref "FR150") (pin "2") (pinfunction "2_2") (pintype "passive"))
      (node (ref "IC76") (pin "5") (pinfunction "EN_5") (pintype "input"))
      (node (ref "IC76") (pin "8") (pinfunction "IN_8") (pintype "input"))
    )
    (net (code "16") (name "Net-(IC77-ADJ{slash}NC)") (class "Default")
      (node (ref "IC77") (pin "3") (pinfunction "ADJ/NC_3") (pintype "passive"))
      (node (ref "R556") (pin "2") (pinfunction "2_2") (pintype "passive"))
      (node (ref "R559") (pin "2") (pinfunction "2_2") (pintype "passive"))
    )
    (net (code "17") (name "Net-(IC77-EN)") (class "Default")
      (node (ref "C925") (pin "2") (pinfunction "2_2") (pintype "passive"))
      (node (ref "FR151") (pin "2") (pinfunction "2_2") (pintype "passive"))
      (node (ref "IC77") (pin "5") (pinfunction "EN_5") (pintype "input"))
      (node (ref "IC77") (pin "8") (pinfunction "IN_8") (pintype "input"))
    )
    (net (code "18") (name "Net-(IC78-ADJ{slash}NC)") (class "Default")
      (node (ref "IC78") (pin "3") (pinfunction "ADJ/NC_3") (pintype "passive"))
      (node (ref "R557") (pin "2") (pinfunction "2_2") (pintype "passive"))
      (node (ref "R560") (pin "2") (pinfunction "2_2") (pintype "passive"))
    )
    (net (code "19") (name "Net-(IC78-EN)") (class "Default")
      (node (ref "C927") (pin "2") (pinfunction "2_2") (pintype "passive"))
      (node (ref "FR152") (pin "2") (pinfunction "2_2") (pintype "passive"))
      (node (ref "IC78") (pin "5") (pinfunction "EN_5") (pintype "input"))
      (node (ref "IC78") (pin "8") (pinfunction "IN_8") (pintype "input"))
    )
    (net (code "20") (name "Net-(IC79-ADJ{slash}NC)") (class "Default")
      (node (ref "IC79") (pin "3") (pinfunction "ADJ/NC_3") (pintype "passive"))
      (node (ref "R561") (pin "1") (pinfunction "1_1") (pintype "passive"))
      (node (ref "R564") (pin "2") (pinfunction "2_2") (pintype "passive"))
    )
    (net (code "21") (name "Net-(IC79-EN)") (class "Default")
      (node (ref "C929") (pin "2") (pinfunction "2_2") (pintype "passive"))
      (node (ref "FR153") (pin "2") (pinfunction "2_2") (pintype "passive"))
      (node (ref "IC79") (pin "5") (pinfunction "EN_5") (pintype "input"))
      (node (ref "IC79") (pin "8") (pinfunction "IN_8") (pintype "input"))
    )
    (net (code "22") (name "Net-(IC80-ADJ{slash}NC)") (class "Default")
      (node (ref "IC80") (pin "3") (pinfunction "ADJ/NC_3") (pintype "passive"))
      (node (ref "R562") (pin "1") (pinfunction "1_1") (pintype "passive"))
      (node (ref "R565") (pin "2") (pinfunction "2_2") (pintype "passive"))
    )
    (net (code "23") (name "Net-(IC80-EN)") (class "Default")
      (node (ref "C931") (pin "2") (pinfunction "2_2") (pintype "passive"))
      (node (ref "FR154") (pin "2") (pinfunction "2_2") (pintype "passive"))
      (node (ref "IC80") (pin "5") (pinfunction "EN_5") (pintype "input"))
      (node (ref "IC80") (pin "8") (pinfunction "IN_8") (pintype "input"))
    )
    (net (code "24") (name "Net-(IC81-ADJ{slash}NC)") (class "Default")
      (node (ref "IC81") (pin "3") (pinfunction "ADJ/NC_3") (pintype "passive"))
      (node (ref "R563") (pin "1") (pinfunction "1_1") (pintype "passive"))
      (node (ref "R566") (pin "2") (pinfunction "2_2") (pintype "passive"))
    )
    (net (code "25") (name "Net-(IC81-EN)") (class "Default")
      (node (ref "C933") (pin "2") (pinfunction "2_2") (pintype "passive"))
      (node (ref "FR155") (pin "2") (pinfunction "2_2") (pintype "passive"))
      (node (ref "IC81") (pin "5") (pinfunction "EN_5") (pintype "input"))
      (node (ref "IC81") (pin "8") (pinfunction "IN_8") (pintype "input"))
    )
    (net (code "26") (name "Net-(IC82-ADJ{slash}NC)") (class "Default")
      (node (ref "IC82") (pin "3") (pinfunction "ADJ/NC_3") (pintype "passive"))
      (node (ref "R569") (pin "1") (pinfunction "1_1") (pintype "passive"))
      (node (ref "R571") (pin "1") (pinfunction "1_1") (pintype "passive"))
    )
    (net (code "27") (name "Net-(IC82-EN)") (class "Default")
      (node (ref "C937") (pin "2") (pinfunction "2_2") (pintype "passive"))
      (node (ref "FR159") (pin "2") (pinfunction "2_2") (pintype "passive"))
      (node (ref "IC82") (pin "5") (pinfunction "EN_5") (pintype "input"))
      (node (ref "IC82") (pin "8") (pinfunction "IN_8") (pintype "input"))
    )
    (net (code "28") (name "Net-(IC83-ADJ{slash}NC)") (class "Default")
      (node (ref "IC83") (pin "3") (pinfunction "ADJ/NC_3") (pintype "passive"))
      (node (ref "R570") (pin "1") (pinfunction "1_1") (pintype "passive"))
      (node (ref "R572") (pin "1") (pinfunction "1_1") (pintype "passive"))
    )
    (net (code "29") (name "Net-(IC83-EN)") (class "Default")
      (node (ref "C939") (pin "2") (pinfunction "2_2") (pintype "passive"))
      (node (ref "FR160") (pin "2") (pinfunction "2_2") (pintype "passive"))
      (node (ref "IC83") (pin "5") (pinfunction "EN_5") (pintype "input"))
      (node (ref "IC83") (pin "8") (pinfunction "IN_8") (pintype "input"))
    )
    (net (code "30") (name "Net-(IC84-ADJ{slash}NC)") (class "Default")
      (node (ref "IC84") (pin "3") (pinfunction "ADJ/NC_3") (pintype "passive"))
      (node (ref "R575") (pin "1") (pinfunction "1_1") (pintype "passive"))
      (node (ref "R576") (pin "1") (pinfunction "1_1") (pintype "passive"))
    )
    (net (code "31") (name "Net-(IC84-EN)") (class "Default")
      (node (ref "C941") (pin "2") (pinfunction "2_2") (pintype "passive"))
      (node (ref "FR162") (pin "2") (pinfunction "2_2") (pintype "passive"))
      (node (ref "IC84") (pin "5") (pinfunction "EN_5") (pintype "input"))
      (node (ref "IC84") (pin "8") (pinfunction "IN_8") (pintype "input"))
    )
    (net (code "32") (name "Net-(IC85-IN)") (class "Default")
      (node (ref "C943") (pin "2") (pinfunction "2_2") (pintype "passive"))
      (node (ref "C944") (pin "2") (pinfunction "2_2") (pintype "passive"))
      (node (ref "FR164") (pin "2") (pinfunction "2_2") (pintype "passive"))
      (node (ref "IC85") (pin "1") (pinfunction "IN_1") (pintype "power_in"))
    )
    (net (code "33") (name "VCC1P4_LMS1") (class "Default")
      (node (ref "C928") (pin "2") (pinfunction "2_2") (pintype "passive"))
      (node (ref "IC78") (pin "1") (pinfunction "OUT_1") (pintype "output"))
      (node (ref "R557") (pin "1") (pinfunction "1_1") (pintype "passive"))
      (node (ref "TP19") (pin "1") (pintype "passive"))
    )
    (net (code "34") (name "VCC1P4_LMS2") (class "Default")
      (node (ref "C924") (pin "2") (pinfunction "2_2") (pintype "passive"))
      (node (ref "IC76") (pin "1") (pinfunction "OUT_1") (pintype "output"))
      (node (ref "R555") (pin "1") (pinfunction "1_1") (pintype "passive"))
      (node (ref "TP17") (pin "1") (pintype "passive"))
    )
    (net (code "35") (name "VCC1P4_LMS3") (class "Default")
      (node (ref "C926") (pin "2") (pinfunction "2_2") (pintype "passive"))
      (node (ref "IC77") (pin "1") (pinfunction "OUT_1") (pintype "output"))
      (node (ref "R556") (pin "1") (pinfunction "1_1") (pintype "passive"))
      (node (ref "TP18") (pin "1") (pintype "passive"))
    )
    (net (code "36") (name "VCC1P8") (class "Default")
      (node (ref "FR156") (pin "1") (pinfunction "1_1") (pintype "passive"))
    )
    (net (code "37") (name "VCC1P8A") (class "Default")
      (node (ref "C938") (pin "2") (pinfunction "2_2") (pintype "passive"))
      (node (ref "FR156") (pin "2") (pinfunction "2_2") (pintype "passive"))
      (node (ref "IC82") (pin "1") (pinfunction "OUT_1") (pintype "output"))
      (node (ref "R569") (pin "2") (pinfunction "2_2") (pintype "passive"))
      (node (ref "TP23") (pin "1") (pintype "passive"))
    )
    (net (code "38") (name "VCC1P8_LMS1") (class "Default")
      (node (ref "C917") (pin "2") (pinfunction "2_2") (pintype "passive"))
      (node (ref "FR149") (pin "2") (pinfunction "2_2") (pintype "passive"))
      (node (ref "FR152") (pin "1") (pinfunction "1_1") (pintype "passive"))
      (node (ref "FR155") (pin "1") (pinfunction "1_1") (pintype "passive"))
      (node (ref "TP16") (pin "1") (pintype "passive"))
    )
    (net (code "39") (name "VCC1P8_LMS2") (class "Default")
      (node (ref "C913") (pin "2") (pinfunction "2_2") (pintype "passive"))
      (node (ref "FR147") (pin "2") (pinfunction "2_2") (pintype "passive"))
      (node (ref "FR150") (pin "1") (pinfunction "1_1") (pintype "passive"))
      (node (ref "FR153") (pin "1") (pinfunction "1_1") (pintype "passive"))
      (node (ref "TP14") (pin "1") (pintype "passive"))
    )
    (net (code "40") (name "VCC1P8_LMS3") (class "Default")
      (node (ref "C914") (pin "2") (pinfunction "2_2") (pintype "passive"))
      (node (ref "FR148") (pin "2") (pinfunction "2_2") (pintype "passive"))
      (node (ref "FR151") (pin "1") (pinfunction "1_1") (pintype "passive"))
      (node (ref "FR154") (pin "1") (pinfunction "1_1") (pintype "passive"))
      (node (ref "TP15") (pin "1") (pintype "passive"))
    )
    (net (code "41") (name "VCC1P25_LMS1") (class "Default")
      (node (ref "C934") (pin "2") (pinfunction "2_2") (pintype "passive"))
      (node (ref "IC81") (pin "1") (pinfunction "OUT_1") (pintype "output"))
      (node (ref "R563") (pin "2") (pinfunction "2_2") (pintype "passive"))
      (node (ref "TP22") (pin "1") (pintype "passive"))
    )
    (net (code "42") (name "VCC1P25_LMS2") (class "Default")
      (node (ref "C930") (pin "2") (pinfunction "2_2") (pintype "passive"))
      (node (ref "IC79") (pin "1") (pinfunction "OUT_1") (pintype "output"))
      (node (ref "R561") (pin "2") (pinfunction "2_2") (pintype "passive"))
      (node (ref "TP20") (pin "1") (pintype "passive"))
    )
    (net (code "43") (name "VCC1P25_LMS3") (class "Default")
      (node (ref "C932") (pin "2") (pinfunction "2_2") (pintype "passive"))
      (node (ref "IC80") (pin "1") (pinfunction "OUT_1") (pintype "output"))
      (node (ref "R562") (pin "2") (pinfunction "2_2") (pintype "passive"))
      (node (ref "TP21") (pin "1") (pintype "passive"))
    )
    (net (code "44") (name "VCC2P5") (class "Default")
      (node (ref "FR157") (pin "1") (pinfunction "1_1") (pintype "passive"))
      (node (ref "FR159") (pin "1") (pinfunction "1_1") (pintype "passive"))
      (node (ref "R568") (pin "2") (pinfunction "2_2") (pintype "passive"))
    )
    (net (code "45") (name "VCC2P5_CLK") (class "Default")
      (node (ref "C940") (pin "2") (pinfunction "2_2") (pintype "passive"))
      (node (ref "FR157") (pin "2") (pinfunction "2_2") (pintype "passive"))
      (node (ref "FR163") (pin "1") (pinfunction "1_1") (pintype "passive"))
      (node (ref "IC83") (pin "1") (pinfunction "OUT_1") (pintype "output"))
      (node (ref "R570") (pin "2") (pinfunction "2_2") (pintype "passive"))
      (node (ref "TP24") (pin "1") (pintype "passive"))
    )
    (net (code "46") (name "VCC2P5_VREF") (class "Default")
      (node (ref "C945") (pin "2") (pinfunction "2_2") (pintype "passive"))
      (node (ref "FR163") (pin "2") (pinfunction "2_2") (pintype "passive"))
      (node (ref "IC85") (pin "2") (pinfunction "OUT_2") (pintype "power_in"))
      (node (ref "TP26") (pin "1") (pintype "passive"))
    )
    (net (code "47") (name "VCC3P3") (class "Default")
      (node (ref "FR160") (pin "1") (pinfunction "1_1") (pintype "passive"))
      (node (ref "FR161") (pin "1") (pinfunction "1_1") (pintype "passive"))
      (node (ref "R546") (pin "1") (pinfunction "1_1") (pintype "passive"))
      (node (ref "R547") (pin "1") (pinfunction "1_1") (pintype "passive"))
      (node (ref "R548") (pin "1") (pinfunction "1_1") (pintype "passive"))
      (node (ref "R567") (pin "2") (pinfunction "2_2") (pintype "passive"))
      (node (ref "R573") (pin "2") (pinfunction "2_2") (pintype "passive"))
    )
    (net (code "48") (name "VCC3P3_BBDAC") (class "Default")
      (node (ref "R573") (pin "1") (pinfunction "1_1") (pintype "passive"))
      (node (ref "R574") (pin "1") (pinfunction "1_1") (pintype "passive"))
    )
    (net (code "49") (name "VCC3P3_CLK") (class "Default")
      (node (ref "C942") (pin "2") (pinfunction "2_2") (pintype "passive"))
      (node (ref "FR161") (pin "2") (pinfunction "2_2") (pintype "passive"))
      (node (ref "FR164") (pin "1") (pinfunction "1_1") (pintype "passive"))
      (node (ref "IC84") (pin "1") (pinfunction "OUT_1") (pintype "output"))
      (node (ref "R574") (pin "2") (pinfunction "2_2") (pintype "passive"))
      (node (ref "R575") (pin "2") (pinfunction "2_2") (pintype "passive"))
      (node (ref "TP25") (pin "1") (pintype "passive"))
    )
    (net (code "50") (name "VCC5P0") (class "Default")
      (node (ref "C911") (pin "2") (pinfunction "2_2") (pintype "passive"))
      (node (ref "C912") (pin "2") (pinfunction "2_2") (pintype "passive"))
      (node (ref "C915") (pin "2") (pinfunction "2_2") (pintype "passive"))
      (node (ref "FR162") (pin "1") (pinfunction "1_1") (pintype "passive"))
      (node (ref "IC73") (pin "7") (pinfunction "VIN_7") (pintype "input"))
      (node (ref "IC74") (pin "7") (pinfunction "VIN_7") (pintype "input"))
      (node (ref "IC75") (pin "7") (pinfunction "VIN_7") (pintype "input"))
    )
    (net (code "51") (name "VDIO_LMS") (class "Default")
      (node (ref "C935") (pin "2") (pinfunction "2_2") (pintype "passive"))
      (node (ref "C936") (pin "1") (pinfunction "1_1") (pintype "passive"))
      (node (ref "FR158") (pin "2") (pinfunction "2_2") (pintype "passive"))
    )
    (net (code "52") (name "VDIO_LMS_FPGA") (class "Default")
      (node (ref "FR158") (pin "1") (pinfunction "1_1") (pintype "passive"))
      (node (ref "R567") (pin "1") (pinfunction "1_1") (pintype "passive"))
      (node (ref "R568") (pin "1") (pinfunction "1_1") (pintype "passive"))
    )
    (net (code "53") (name "unconnected-(IC76-NC-Pad2)") (class "Default")
      (node (ref "IC76") (pin "2") (pinfunction "NC_2") (pintype "passive+no_connect"))
    )
    (net (code "54") (name "unconnected-(IC76-NC-Pad6)") (class "Default")
      (node (ref "IC76") (pin "6") (pinfunction "NC_6") (pintype "passive+no_connect"))
    )
    (net (code "55") (name "unconnected-(IC76-NC-Pad7)") (class "Default")
      (node (ref "IC76") (pin "7") (pinfunction "NC_7") (pintype "passive+no_connect"))
    )
    (net (code "56") (name "unconnected-(IC77-NC-Pad2)") (class "Default")
      (node (ref "IC77") (pin "2") (pinfunction "NC_2") (pintype "passive+no_connect"))
    )
    (net (code "57") (name "unconnected-(IC77-NC-Pad6)") (class "Default")
      (node (ref "IC77") (pin "6") (pinfunction "NC_6") (pintype "passive+no_connect"))
    )
    (net (code "58") (name "unconnected-(IC77-NC-Pad7)") (class "Default")
      (node (ref "IC77") (pin "7") (pinfunction "NC_7") (pintype "passive+no_connect"))
    )
    (net (code "59") (name "unconnected-(IC78-NC-Pad2)") (class "Default")
      (node (ref "IC78") (pin "2") (pinfunction "NC_2") (pintype "passive+no_connect"))
    )
    (net (code "60") (name "unconnected-(IC78-NC-Pad6)") (class "Default")
      (node (ref "IC78") (pin "6") (pinfunction "NC_6") (pintype "passive+no_connect"))
    )
    (net (code "61") (name "unconnected-(IC78-NC-Pad7)") (class "Default")
      (node (ref "IC78") (pin "7") (pinfunction "NC_7") (pintype "passive+no_connect"))
    )
    (net (code "62") (name "unconnected-(IC79-NC-Pad2)") (class "Default")
      (node (ref "IC79") (pin "2") (pinfunction "NC_2") (pintype "passive+no_connect"))
    )
    (net (code "63") (name "unconnected-(IC79-NC-Pad6)") (class "Default")
      (node (ref "IC79") (pin "6") (pinfunction "NC_6") (pintype "passive+no_connect"))
    )
    (net (code "64") (name "unconnected-(IC79-NC-Pad7)") (class "Default")
      (node (ref "IC79") (pin "7") (pinfunction "NC_7") (pintype "passive+no_connect"))
    )
    (net (code "65") (name "unconnected-(IC80-NC-Pad2)") (class "Default")
      (node (ref "IC80") (pin "2") (pinfunction "NC_2") (pintype "passive+no_connect"))
    )
    (net (code "66") (name "unconnected-(IC80-NC-Pad6)") (class "Default")
      (node (ref "IC80") (pin "6") (pinfunction "NC_6") (pintype "passive+no_connect"))
    )
    (net (code "67") (name "unconnected-(IC80-NC-Pad7)") (class "Default")
      (node (ref "IC80") (pin "7") (pinfunction "NC_7") (pintype "passive+no_connect"))
    )
    (net (code "68") (name "unconnected-(IC81-NC-Pad2)") (class "Default")
      (node (ref "IC81") (pin "2") (pinfunction "NC_2") (pintype "passive+no_connect"))
    )
    (net (code "69") (name "unconnected-(IC81-NC-Pad6)") (class "Default")
      (node (ref "IC81") (pin "6") (pinfunction "NC_6") (pintype "passive+no_connect"))
    )
    (net (code "70") (name "unconnected-(IC81-NC-Pad7)") (class "Default")
      (node (ref "IC81") (pin "7") (pinfunction "NC_7") (pintype "passive+no_connect"))
    )
    (net (code "71") (name "unconnected-(IC82-NC-Pad2)") (class "Default")
      (node (ref "IC82") (pin "2") (pinfunction "NC_2") (pintype "passive+no_connect"))
    )
    (net (code "72") (name "unconnected-(IC82-NC-Pad6)") (class "Default")
      (node (ref "IC82") (pin "6") (pinfunction "NC_6") (pintype "passive+no_connect"))
    )
    (net (code "73") (name "unconnected-(IC82-NC-Pad7)") (class "Default")
      (node (ref "IC82") (pin "7") (pinfunction "NC_7") (pintype "passive+no_connect"))
    )
    (net (code "74") (name "unconnected-(IC83-NC-Pad2)") (class "Default")
      (node (ref "IC83") (pin "2") (pinfunction "NC_2") (pintype "passive+no_connect"))
    )
    (net (code "75") (name "unconnected-(IC83-NC-Pad6)") (class "Default")
      (node (ref "IC83") (pin "6") (pinfunction "NC_6") (pintype "passive+no_connect"))
    )
    (net (code "76") (name "unconnected-(IC83-NC-Pad7)") (class "Default")
      (node (ref "IC83") (pin "7") (pinfunction "NC_7") (pintype "passive+no_connect"))
    )
    (net (code "77") (name "unconnected-(IC84-NC-Pad2)") (class "Default")
      (node (ref "IC84") (pin "2") (pinfunction "NC_2") (pintype "passive+no_connect"))
    )
    (net (code "78") (name "unconnected-(IC84-NC-Pad6)") (class "Default")
      (node (ref "IC84") (pin "6") (pinfunction "NC_6") (pintype "passive+no_connect"))
    )
    (net (code "79") (name "unconnected-(IC84-NC-Pad7)") (class "Default")
      (node (ref "IC84") (pin "7") (pinfunction "NC_7") (pintype "passive+no_connect"))
    )
  )
)
